# eae-pld.net
KiCad netlist of a schematic drawn in EAGLE
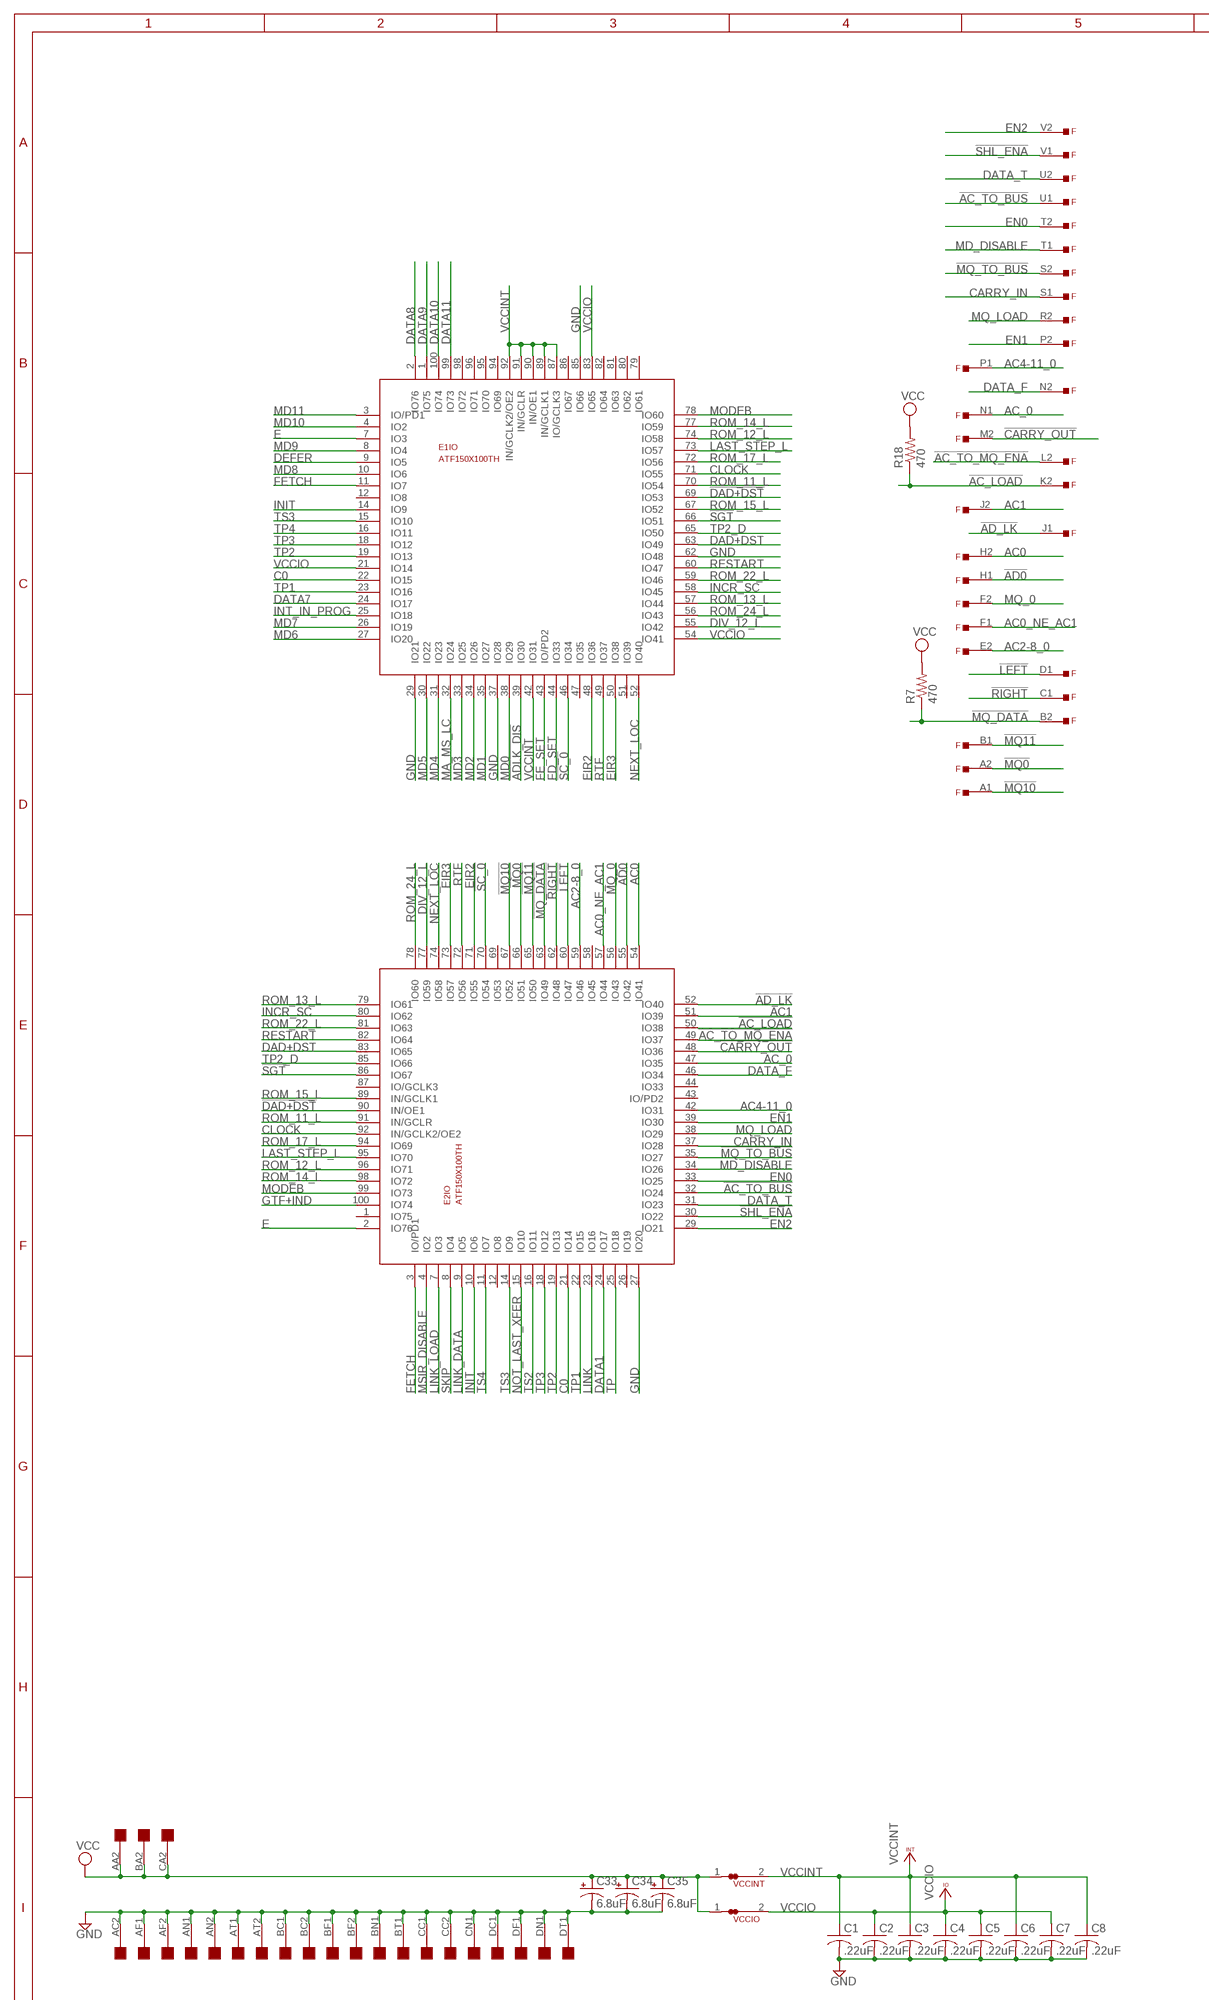
[diagram p0: schematic, sheet 1, part 1 of 2]
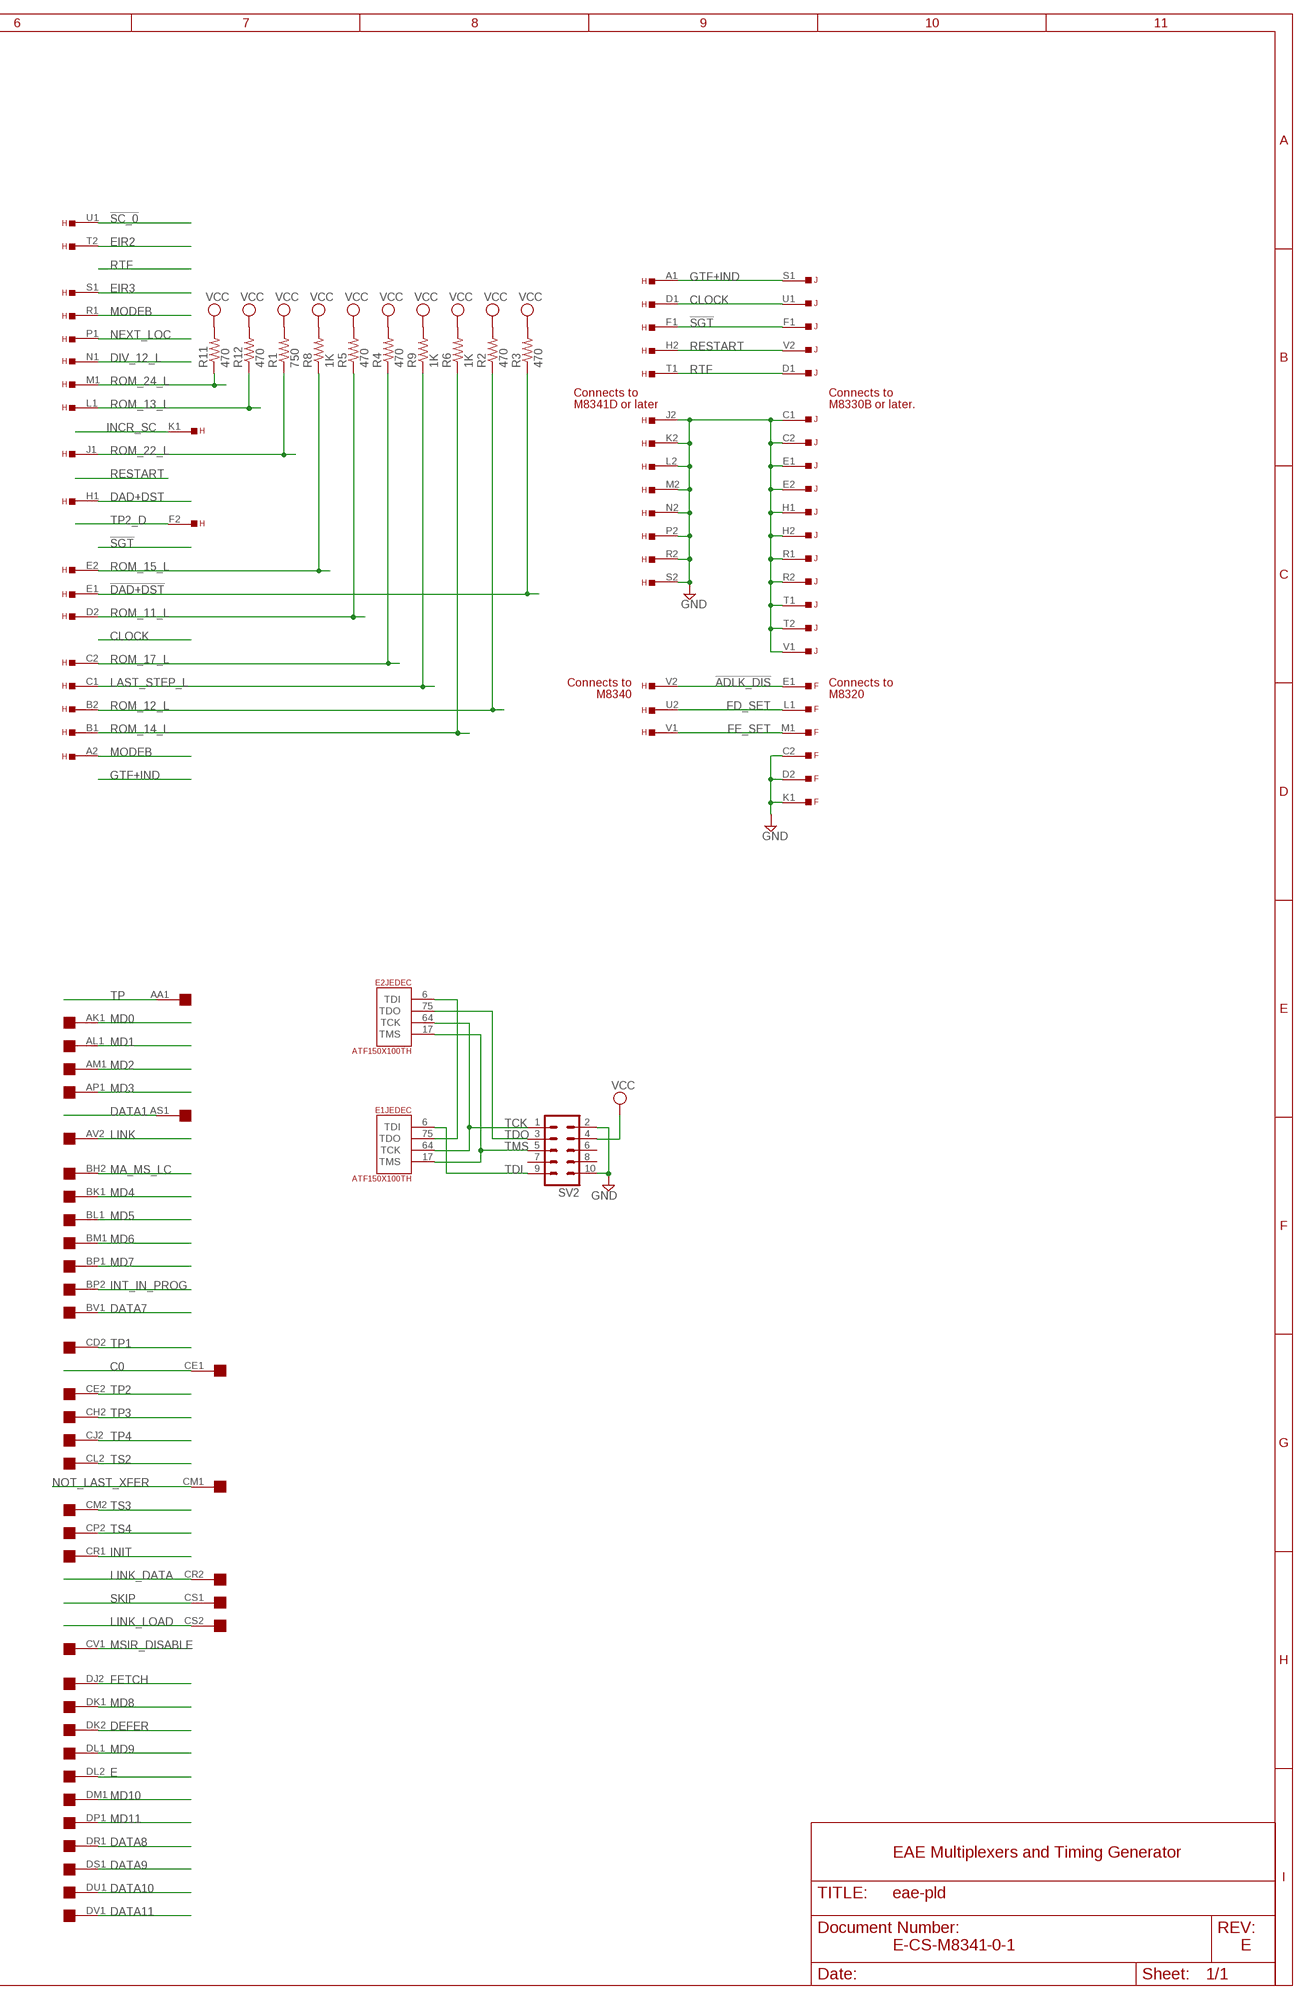
[diagram p1: schematic, sheet 1, part 2 of 2]

(export (version "E")
  (design (tool "Eeschema 10.0.6"))
  (components
    (comp (ref "C1")
      (value ".22uF")
      (footprint "eagle-import:C063-025X075")
      (libsource (lib "eagle-import") (part "C-US"))
    )
    (comp (ref "C2")
      (value ".22uF")
      (footprint "eagle-import:C063-025X075")
      (libsource (lib "eagle-import") (part "C-US"))
    )
    (comp (ref "C3")
      (value ".22uF")
      (footprint "eagle-import:C063-025X075")
      (libsource (lib "eagle-import") (part "C-US"))
    )
    (comp (ref "C4")
      (value ".22uF")
      (footprint "eagle-import:C063-025X075")
      (libsource (lib "eagle-import") (part "C-US"))
    )
    (comp (ref "C5")
      (value ".22uF")
      (footprint "eagle-import:C063-025X075")
      (libsource (lib "eagle-import") (part "C-US"))
    )
    (comp (ref "C6")
      (value ".22uF")
      (footprint "eagle-import:C063-025X075")
      (libsource (lib "eagle-import") (part "C-US"))
    )
    (comp (ref "C7")
      (value ".22uF")
      (footprint "eagle-import:C063-025X075")
      (libsource (lib "eagle-import") (part "C-US"))
    )
    (comp (ref "C8")
      (value ".22uF")
      (footprint "eagle-import:C063-025X075")
      (libsource (lib "eagle-import") (part "C-US"))
    )
    (comp (ref "C33")
      (value "6.8uF")
      (footprint "eagle-import:E12-8")
      (libsource (lib "eagle-import") (part "CPOL-USE20-8AXIAL"))
    )
    (comp (ref "C34")
      (value "6.8uF")
      (footprint "eagle-import:E12-8")
      (libsource (lib "eagle-import") (part "CPOL-USE20-8AXIAL"))
    )
    (comp (ref "C35")
      (value "6.8uF")
      (footprint "eagle-import:E12-8")
      (libsource (lib "eagle-import") (part "CPOL-USE20-8AXIAL"))
    )
    (comp (ref "E1")
      (value "ATF150X100TH")
      (footprint "eagle-import:TH-100")
      (libsource (lib "eagle-import") (part "ATF150X100TH"))
    )
    (comp (ref "E2")
      (value "ATF150X100TH")
      (footprint "eagle-import:TH-100")
      (libsource (lib "eagle-import") (part "ATF150X100TH"))
    )
    (comp (ref "F")
      (value "EDGE-TOP")
      (footprint "eagle-import:EDGE-CON2")
      (libsource (lib "eagle-import") (part "EDGE-TOP"))
    )
    (comp (ref "H")
      (value "EDGE-TOP")
      (footprint "eagle-import:EDGE-CON2")
      (libsource (lib "eagle-import") (part "EDGE-TOP"))
    )
    (comp (ref "J")
      (value "EDGE-TOP")
      (footprint "eagle-import:EDGE-CON2")
      (libsource (lib "eagle-import") (part "EDGE-TOP"))
    )
    (comp (ref "R1")
      (value "750")
      (footprint "eagle-import:0207_10")
      (libsource (lib "eagle-import") (part "R-US_0207/10"))
    )
    (comp (ref "R2")
      (value "470")
      (footprint "eagle-import:0207_10")
      (libsource (lib "eagle-import") (part "R-US_0207/10"))
    )
    (comp (ref "R3")
      (value "470")
      (footprint "eagle-import:0207_10")
      (libsource (lib "eagle-import") (part "R-US_0207/10"))
    )
    (comp (ref "R4")
      (value "470")
      (footprint "eagle-import:0207_10")
      (libsource (lib "eagle-import") (part "R-US_0207/10"))
    )
    (comp (ref "R5")
      (value "470")
      (footprint "eagle-import:0207_10")
      (libsource (lib "eagle-import") (part "R-US_0207/10"))
    )
    (comp (ref "R6")
      (value "1K")
      (footprint "eagle-import:0207_10")
      (libsource (lib "eagle-import") (part "R-US_0207/10"))
    )
    (comp (ref "R7")
      (value "470")
      (footprint "eagle-import:0207_10")
      (libsource (lib "eagle-import") (part "R-US_0207/10"))
    )
    (comp (ref "R8")
      (value "1K")
      (footprint "eagle-import:0207_10")
      (libsource (lib "eagle-import") (part "R-US_0207/10"))
    )
    (comp (ref "R9")
      (value "1K")
      (footprint "eagle-import:0207_10")
      (libsource (lib "eagle-import") (part "R-US_0207/10"))
    )
    (comp (ref "R11")
      (value "470")
      (footprint "eagle-import:0207_10")
      (libsource (lib "eagle-import") (part "R-US_0207/10"))
    )
    (comp (ref "R12")
      (value "470")
      (footprint "eagle-import:0207_10")
      (libsource (lib "eagle-import") (part "R-US_0207/10"))
    )
    (comp (ref "R18")
      (value "470")
      (footprint "eagle-import:0207_10")
      (libsource (lib "eagle-import") (part "R-US_0207/10"))
    )
    (comp (ref "SV2")
      (value "ML10")
      (footprint "eagle-import:ML10")
      (libsource (lib "eagle-import") (part "ML10"))
    )
    (comp (ref "U$1")
      (value "QUAD")
      (footprint "eagle-import:EDGE-CON8")
      (libsource (lib "eagle-import") (part "QUAD"))
    )
    (comp (ref "VCCINT")
      (value "JUMPER-NC1")
      (footprint "eagle-import:NC1")
      (libsource (lib "eagle-import") (part "JUMPER-NC1"))
    )
    (comp (ref "VCCIO")
      (value "JUMPER-NC1")
      (footprint "eagle-import:NC1")
      (libsource (lib "eagle-import") (part "JUMPER-NC1"))
    )
  )
  (nets
    (net (code "1") (name "/AC0") (class "Default")
      (node (ref "E2") (pin "54") (pinfunction "IO41_54") (pintype "bidirectional"))
      (node (ref "F") (pin "H2") (pinfunction "P_H2") (pintype "passive"))
    )
    (net (code "2") (name "/AC0_NE_AC1") (class "Default")
      (node (ref "E2") (pin "57") (pinfunction "IO44_57") (pintype "bidirectional"))
      (node (ref "F") (pin "F1") (pinfunction "P_F1") (pintype "passive"))
    )
    (net (code "3") (name "/AC1") (class "Default")
      (node (ref "E2") (pin "51") (pinfunction "IO39_51") (pintype "bidirectional"))
      (node (ref "F") (pin "J2") (pinfunction "P_J2") (pintype "passive"))
    )
    (net (code "4") (name "/AC2-8_0") (class "Default")
      (node (ref "E2") (pin "59") (pinfunction "IO46_59") (pintype "bidirectional"))
      (node (ref "F") (pin "E2") (pinfunction "P_E2") (pintype "passive"))
    )
    (net (code "5") (name "/AC4-11_0") (class "Default")
      (node (ref "E2") (pin "42") (pinfunction "IO31_42") (pintype "bidirectional"))
      (node (ref "F") (pin "P1") (pinfunction "P_P1") (pintype "passive"))
    )
    (net (code "6") (name "/AC_0") (class "Default")
      (node (ref "E2") (pin "47") (pinfunction "IO35_47") (pintype "bidirectional"))
      (node (ref "F") (pin "N1") (pinfunction "P_N1") (pintype "passive"))
    )
    (net (code "7") (name "/C0") (class "Default")
      (node (ref "E1") (pin "22") (pinfunction "IO15_22") (pintype "bidirectional"))
      (node (ref "E2") (pin "21") (pinfunction "IO14_21") (pintype "bidirectional"))
      (node (ref "U$1") (pin "CE1") (pinfunction "1_CE1") (pintype "bidirectional"))
    )
    (net (code "8") (name "/CARRY_IN") (class "Default")
      (node (ref "E2") (pin "37") (pinfunction "IO28_37") (pintype "bidirectional"))
      (node (ref "F") (pin "S1") (pinfunction "P_S1") (pintype "passive"))
    )
    (net (code "9") (name "/CLOCK") (class "Default")
      (node (ref "E1") (pin "71") (pinfunction "IO55_71") (pintype "bidirectional"))
      (node (ref "E2") (pin "92") (pinfunction "IN/GCLK2/OE2_92") (pintype "input"))
      (node (ref "H") (pin "D1") (pinfunction "P_D1") (pintype "passive"))
      (node (ref "J") (pin "U1") (pinfunction "P_U1") (pintype "passive"))
    )
    (net (code "10") (name "/DAD+DST") (class "Default")
      (node (ref "E1") (pin "63") (pinfunction "IO49_63") (pintype "bidirectional"))
      (node (ref "E2") (pin "83") (pinfunction "IO65_83") (pintype "bidirectional"))
      (node (ref "H") (pin "H1") (pinfunction "P_H1") (pintype "passive"))
    )
    (net (code "11") (name "/DATA1") (class "Default")
      (node (ref "E2") (pin "24") (pinfunction "IO17_24") (pintype "bidirectional"))
      (node (ref "U$1") (pin "AS1") (pinfunction "1_AS1") (pintype "bidirectional"))
    )
    (net (code "12") (name "/DATA7") (class "Default")
      (node (ref "E1") (pin "24") (pinfunction "IO17_24") (pintype "bidirectional"))
      (node (ref "U$1") (pin "BV1") (pinfunction "1_BV1") (pintype "bidirectional"))
    )
    (net (code "13") (name "/DATA8") (class "Default")
      (node (ref "E1") (pin "2") (pinfunction "IO76_2") (pintype "bidirectional"))
      (node (ref "U$1") (pin "DR1") (pinfunction "1_DR1") (pintype "bidirectional"))
    )
    (net (code "14") (name "/DATA9") (class "Default")
      (node (ref "E1") (pin "1") (pinfunction "IO75_1") (pintype "bidirectional"))
      (node (ref "U$1") (pin "DS1") (pinfunction "1_DS1") (pintype "bidirectional"))
    )
    (net (code "15") (name "/DATA10") (class "Default")
      (node (ref "E1") (pin "100") (pinfunction "IO74_100") (pintype "bidirectional"))
      (node (ref "U$1") (pin "DU1") (pinfunction "1_DU1") (pintype "bidirectional"))
    )
    (net (code "16") (name "/DATA11") (class "Default")
      (node (ref "E1") (pin "99") (pinfunction "IO73_99") (pintype "bidirectional"))
      (node (ref "U$1") (pin "DV1") (pinfunction "1_DV1") (pintype "bidirectional"))
    )
    (net (code "17") (name "/DATA_F") (class "Default")
      (node (ref "E2") (pin "46") (pinfunction "IO34_46") (pintype "bidirectional"))
      (node (ref "F") (pin "N2") (pinfunction "P_N2") (pintype "passive"))
    )
    (net (code "18") (name "/DATA_T") (class "Default")
      (node (ref "E2") (pin "31") (pinfunction "IO23_31") (pintype "bidirectional"))
      (node (ref "F") (pin "U2") (pinfunction "P_U2") (pintype "passive"))
    )
    (net (code "19") (name "/DEFER") (class "Default")
      (node (ref "E1") (pin "9") (pinfunction "IO5_9") (pintype "bidirectional"))
      (node (ref "U$1") (pin "DK2") (pinfunction "1_DK2") (pintype "bidirectional"))
    )
    (net (code "20") (name "/DIV_12_L") (class "Default")
      (node (ref "E1") (pin "55") (pinfunction "IO42_55") (pintype "bidirectional"))
      (node (ref "E2") (pin "77") (pinfunction "IO59_77") (pintype "bidirectional"))
      (node (ref "H") (pin "N1") (pinfunction "P_N1") (pintype "passive"))
    )
    (net (code "21") (name "/E") (class "Default")
      (node (ref "E1") (pin "7") (pinfunction "IO3_7") (pintype "bidirectional"))
      (node (ref "E2") (pin "2") (pinfunction "IO76_2") (pintype "bidirectional"))
      (node (ref "U$1") (pin "DL2") (pinfunction "1_DL2") (pintype "bidirectional"))
    )
    (net (code "22") (name "/EIR2") (class "Default")
      (node (ref "E1") (pin "48") (pinfunction "IO36_48") (pintype "bidirectional"))
      (node (ref "E2") (pin "71") (pinfunction "IO55_71") (pintype "bidirectional"))
      (node (ref "H") (pin "T2") (pinfunction "P_T2") (pintype "passive"))
    )
    (net (code "23") (name "/EIR3") (class "Default")
      (node (ref "E1") (pin "50") (pinfunction "IO38_50") (pintype "bidirectional"))
      (node (ref "E2") (pin "73") (pinfunction "IO57_73") (pintype "bidirectional"))
      (node (ref "H") (pin "S1") (pinfunction "P_S1") (pintype "passive"))
    )
    (net (code "24") (name "/EN0") (class "Default")
      (node (ref "E2") (pin "33") (pinfunction "IO25_33") (pintype "bidirectional"))
      (node (ref "F") (pin "T2") (pinfunction "P_T2") (pintype "passive"))
    )
    (net (code "25") (name "/EN1") (class "Default")
      (node (ref "E2") (pin "39") (pinfunction "IO30_39") (pintype "bidirectional"))
      (node (ref "F") (pin "P2") (pinfunction "P_P2") (pintype "passive"))
    )
    (net (code "26") (name "/EN2") (class "Default")
      (node (ref "E2") (pin "29") (pinfunction "IO21_29") (pintype "bidirectional"))
      (node (ref "F") (pin "V2") (pinfunction "P_V2") (pintype "passive"))
    )
    (net (code "27") (name "/FD_SET") (class "Default")
      (node (ref "E1") (pin "44") (pinfunction "IO33_44") (pintype "bidirectional"))
      (node (ref "F") (pin "L1") (pinfunction "P_L1") (pintype "passive"))
      (node (ref "H") (pin "U2") (pinfunction "P_U2") (pintype "passive"))
    )
    (net (code "28") (name "/FETCH") (class "Default")
      (node (ref "E1") (pin "11") (pinfunction "IO7_11") (pintype "bidirectional"))
      (node (ref "E2") (pin "3") (pinfunction "IO/PD1_3") (pintype "bidirectional"))
      (node (ref "U$1") (pin "DJ2") (pinfunction "1_DJ2") (pintype "bidirectional"))
    )
    (net (code "29") (name "/FE_SET") (class "Default")
      (node (ref "E1") (pin "43") (pinfunction "IO/PD2_43") (pintype "bidirectional"))
      (node (ref "F") (pin "M1") (pinfunction "P_M1") (pintype "passive"))
      (node (ref "H") (pin "V1") (pinfunction "P_V1") (pintype "passive"))
    )
    (net (code "30") (name "/GTF+IND") (class "Default")
      (node (ref "E2") (pin "100") (pinfunction "IO74_100") (pintype "bidirectional"))
      (node (ref "H") (pin "A1") (pinfunction "P_A1") (pintype "passive"))
      (node (ref "J") (pin "S1") (pinfunction "P_S1") (pintype "passive"))
    )
    (net (code "31") (name "/INCR_SC") (class "Default")
      (node (ref "E1") (pin "58") (pinfunction "IO45_58") (pintype "bidirectional"))
      (node (ref "E2") (pin "80") (pinfunction "IO62_80") (pintype "bidirectional"))
      (node (ref "H") (pin "K1") (pinfunction "P_K1") (pintype "passive"))
    )
    (net (code "32") (name "/INIT") (class "Default")
      (node (ref "E1") (pin "14") (pinfunction "IO9_14") (pintype "bidirectional"))
      (node (ref "E2") (pin "10") (pinfunction "IO6_10") (pintype "bidirectional"))
      (node (ref "U$1") (pin "CR1") (pinfunction "1_CR1") (pintype "bidirectional"))
    )
    (net (code "33") (name "/INT_IN_PROG") (class "Default")
      (node (ref "E1") (pin "25") (pinfunction "IO18_25") (pintype "bidirectional"))
      (node (ref "U$1") (pin "BP2") (pinfunction "1_BP2") (pintype "bidirectional"))
    )
    (net (code "34") (name "/LAST_STEP_L") (class "Default")
      (node (ref "E1") (pin "73") (pinfunction "IO57_73") (pintype "bidirectional"))
      (node (ref "E2") (pin "95") (pinfunction "IO70_95") (pintype "bidirectional"))
      (node (ref "H") (pin "C1") (pinfunction "P_C1") (pintype "passive"))
      (node (ref "R9") (pin "1") (pinfunction "1_1") (pintype "passive"))
    )
    (net (code "35") (name "/LINK") (class "Default")
      (node (ref "E2") (pin "23") (pinfunction "IO16_23") (pintype "bidirectional"))
      (node (ref "U$1") (pin "AV2") (pinfunction "1_AV2") (pintype "bidirectional"))
    )
    (net (code "36") (name "/LINK_DATA") (class "Default")
      (node (ref "E2") (pin "9") (pinfunction "IO5_9") (pintype "bidirectional"))
      (node (ref "U$1") (pin "CR2") (pinfunction "1_CR2") (pintype "bidirectional"))
    )
    (net (code "37") (name "/LINK_LOAD") (class "Default")
      (node (ref "E2") (pin "7") (pinfunction "IO3_7") (pintype "bidirectional"))
      (node (ref "U$1") (pin "CS2") (pinfunction "1_CS2") (pintype "bidirectional"))
    )
    (net (code "38") (name "/MA_MS_LC") (class "Default")
      (node (ref "E1") (pin "32") (pinfunction "IO24_32") (pintype "bidirectional"))
      (node (ref "U$1") (pin "BH2") (pinfunction "1_BH2") (pintype "bidirectional"))
    )
    (net (code "39") (name "/MD0") (class "Default")
      (node (ref "E1") (pin "38") (pinfunction "IO29_38") (pintype "bidirectional"))
      (node (ref "U$1") (pin "AK1") (pinfunction "1_AK1") (pintype "bidirectional"))
    )
    (net (code "40") (name "/MD1") (class "Default")
      (node (ref "E1") (pin "35") (pinfunction "IO27_35") (pintype "bidirectional"))
      (node (ref "U$1") (pin "AL1") (pinfunction "1_AL1") (pintype "bidirectional"))
    )
    (net (code "41") (name "/MD2") (class "Default")
      (node (ref "E1") (pin "34") (pinfunction "IO26_34") (pintype "bidirectional"))
      (node (ref "U$1") (pin "AM1") (pinfunction "1_AM1") (pintype "bidirectional"))
    )
    (net (code "42") (name "/MD3") (class "Default")
      (node (ref "E1") (pin "33") (pinfunction "IO25_33") (pintype "bidirectional"))
      (node (ref "U$1") (pin "AP1") (pinfunction "1_AP1") (pintype "bidirectional"))
    )
    (net (code "43") (name "/MD4") (class "Default")
      (node (ref "E1") (pin "31") (pinfunction "IO23_31") (pintype "bidirectional"))
      (node (ref "U$1") (pin "BK1") (pinfunction "1_BK1") (pintype "bidirectional"))
    )
    (net (code "44") (name "/MD5") (class "Default")
      (node (ref "E1") (pin "30") (pinfunction "IO22_30") (pintype "bidirectional"))
      (node (ref "U$1") (pin "BL1") (pinfunction "1_BL1") (pintype "bidirectional"))
    )
    (net (code "45") (name "/MD6") (class "Default")
      (node (ref "E1") (pin "27") (pinfunction "IO20_27") (pintype "bidirectional"))
      (node (ref "U$1") (pin "BM1") (pinfunction "1_BM1") (pintype "bidirectional"))
    )
    (net (code "46") (name "/MD7") (class "Default")
      (node (ref "E1") (pin "26") (pinfunction "IO19_26") (pintype "bidirectional"))
      (node (ref "U$1") (pin "BP1") (pinfunction "1_BP1") (pintype "bidirectional"))
    )
    (net (code "47") (name "/MD8") (class "Default")
      (node (ref "E1") (pin "10") (pinfunction "IO6_10") (pintype "bidirectional"))
      (node (ref "U$1") (pin "DK1") (pinfunction "1_DK1") (pintype "bidirectional"))
    )
    (net (code "48") (name "/MD9") (class "Default")
      (node (ref "E1") (pin "8") (pinfunction "IO4_8") (pintype "bidirectional"))
      (node (ref "U$1") (pin "DL1") (pinfunction "1_DL1") (pintype "bidirectional"))
    )
    (net (code "49") (name "/MD10") (class "Default")
      (node (ref "E1") (pin "4") (pinfunction "IO2_4") (pintype "bidirectional"))
      (node (ref "U$1") (pin "DM1") (pinfunction "1_DM1") (pintype "bidirectional"))
    )
    (net (code "50") (name "/MD11") (class "Default")
      (node (ref "E1") (pin "3") (pinfunction "IO/PD1_3") (pintype "bidirectional"))
      (node (ref "U$1") (pin "DP1") (pinfunction "1_DP1") (pintype "bidirectional"))
    )
    (net (code "51") (name "/MD_DISABLE") (class "Default")
      (node (ref "E2") (pin "34") (pinfunction "IO26_34") (pintype "bidirectional"))
      (node (ref "F") (pin "T1") (pinfunction "P_T1") (pintype "passive"))
    )
    (net (code "52") (name "/MODEB") (class "Default")
      (node (ref "E1") (pin "78") (pinfunction "IO60_78") (pintype "bidirectional"))
      (node (ref "E2") (pin "99") (pinfunction "IO73_99") (pintype "bidirectional"))
      (node (ref "H") (pin "A2") (pinfunction "P_A2") (pintype "passive"))
      (node (ref "H") (pin "R1") (pinfunction "P_R1") (pintype "passive"))
    )
    (net (code "53") (name "/MQ_0") (class "Default")
      (node (ref "E2") (pin "56") (pinfunction "IO43_56") (pintype "bidirectional"))
      (node (ref "F") (pin "F2") (pinfunction "P_F2") (pintype "passive"))
    )
    (net (code "54") (name "/MQ_LOAD") (class "Default")
      (node (ref "E2") (pin "38") (pinfunction "IO29_38") (pintype "bidirectional"))
      (node (ref "F") (pin "R2") (pinfunction "P_R2") (pintype "passive"))
    )
    (net (code "55") (name "/MSIR_DISABLE") (class "Default")
      (node (ref "E2") (pin "4") (pinfunction "IO2_4") (pintype "bidirectional"))
      (node (ref "U$1") (pin "CV1") (pinfunction "1_CV1") (pintype "bidirectional"))
    )
    (net (code "56") (name "/NEXT_LOC") (class "Default")
      (node (ref "E1") (pin "52") (pinfunction "IO40_52") (pintype "bidirectional"))
      (node (ref "E2") (pin "74") (pinfunction "IO58_74") (pintype "bidirectional"))
      (node (ref "H") (pin "P1") (pinfunction "P_P1") (pintype "passive"))
    )
    (net (code "57") (name "/NOT_LAST_XFER") (class "Default")
      (node (ref "E2") (pin "15") (pinfunction "IO10_15") (pintype "bidirectional"))
      (node (ref "U$1") (pin "CM1") (pinfunction "1_CM1") (pintype "bidirectional"))
    )
    (net (code "58") (name "/RESTART") (class "Default")
      (node (ref "E1") (pin "60") (pinfunction "IO47_60") (pintype "bidirectional"))
      (node (ref "E2") (pin "82") (pinfunction "IO64_82") (pintype "bidirectional"))
      (node (ref "H") (pin "H2") (pinfunction "P_H2") (pintype "passive"))
      (node (ref "J") (pin "V2") (pinfunction "P_V2") (pintype "passive"))
    )
    (net (code "59") (name "/ROM_11_L") (class "Default")
      (node (ref "E1") (pin "70") (pinfunction "IO54_70") (pintype "bidirectional"))
      (node (ref "E2") (pin "91") (pinfunction "IN/GCLR_91") (pintype "input"))
      (node (ref "H") (pin "D2") (pinfunction "P_D2") (pintype "passive"))
      (node (ref "R5") (pin "1") (pinfunction "1_1") (pintype "passive"))
    )
    (net (code "60") (name "/ROM_12_L") (class "Default")
      (node (ref "E1") (pin "74") (pinfunction "IO58_74") (pintype "bidirectional"))
      (node (ref "E2") (pin "96") (pinfunction "IO71_96") (pintype "bidirectional"))
      (node (ref "H") (pin "B2") (pinfunction "P_B2") (pintype "passive"))
      (node (ref "R2") (pin "1") (pinfunction "1_1") (pintype "passive"))
    )
    (net (code "61") (name "/ROM_13_L") (class "Default")
      (node (ref "E1") (pin "57") (pinfunction "IO44_57") (pintype "bidirectional"))
      (node (ref "E2") (pin "79") (pinfunction "IO61_79") (pintype "bidirectional"))
      (node (ref "H") (pin "L1") (pinfunction "P_L1") (pintype "passive"))
      (node (ref "R12") (pin "1") (pinfunction "1_1") (pintype "passive"))
    )
    (net (code "62") (name "/ROM_14_L") (class "Default")
      (node (ref "E1") (pin "77") (pinfunction "IO59_77") (pintype "bidirectional"))
      (node (ref "E2") (pin "98") (pinfunction "IO72_98") (pintype "bidirectional"))
      (node (ref "H") (pin "B1") (pinfunction "P_B1") (pintype "passive"))
      (node (ref "R6") (pin "1") (pinfunction "1_1") (pintype "passive"))
    )
    (net (code "63") (name "/ROM_15_L") (class "Default")
      (node (ref "E1") (pin "67") (pinfunction "IO52_67") (pintype "bidirectional"))
      (node (ref "E2") (pin "89") (pinfunction "IN/GCLK1_89") (pintype "input"))
      (node (ref "H") (pin "E2") (pinfunction "P_E2") (pintype "passive"))
      (node (ref "R8") (pin "1") (pinfunction "1_1") (pintype "passive"))
    )
    (net (code "64") (name "/ROM_17_L") (class "Default")
      (node (ref "E1") (pin "72") (pinfunction "IO56_72") (pintype "bidirectional"))
      (node (ref "E2") (pin "94") (pinfunction "IO69_94") (pintype "bidirectional"))
      (node (ref "H") (pin "C2") (pinfunction "P_C2") (pintype "passive"))
      (node (ref "R4") (pin "1") (pinfunction "1_1") (pintype "passive"))
    )
    (net (code "65") (name "/ROM_22_L") (class "Default")
      (node (ref "E1") (pin "59") (pinfunction "IO46_59") (pintype "bidirectional"))
      (node (ref "E2") (pin "81") (pinfunction "IO63_81") (pintype "bidirectional"))
      (node (ref "H") (pin "J1") (pinfunction "P_J1") (pintype "passive"))
      (node (ref "R1") (pin "1") (pinfunction "1_1") (pintype "passive"))
    )
    (net (code "66") (name "/ROM_24_L") (class "Default")
      (node (ref "E1") (pin "56") (pinfunction "IO43_56") (pintype "bidirectional"))
      (node (ref "E2") (pin "78") (pinfunction "IO60_78") (pintype "bidirectional"))
      (node (ref "H") (pin "M1") (pinfunction "P_M1") (pintype "passive"))
      (node (ref "R11") (pin "1") (pinfunction "1_1") (pintype "passive"))
    )
    (net (code "67") (name "/RTF") (class "Default")
      (node (ref "E1") (pin "49") (pinfunction "IO37_49") (pintype "bidirectional"))
      (node (ref "E2") (pin "72") (pinfunction "IO56_72") (pintype "bidirectional"))
      (node (ref "H") (pin "T1") (pinfunction "P_T1") (pintype "passive"))
      (node (ref "J") (pin "D1") (pinfunction "P_D1") (pintype "passive"))
    )
    (net (code "68") (name "/SKIP") (class "Default")
      (node (ref "E2") (pin "8") (pinfunction "IO4_8") (pintype "bidirectional"))
      (node (ref "U$1") (pin "CS1") (pinfunction "1_CS1") (pintype "bidirectional"))
    )
    (net (code "69") (name "/TCK") (class "Default")
      (node (ref "E1") (pin "64") (pinfunction "TCK_64") (pintype "bidirectional"))
      (node (ref "E2") (pin "64") (pinfunction "TCK_64") (pintype "bidirectional"))
      (node (ref "SV2") (pin "1") (pinfunction "1_1") (pintype "passive"))
    )
    (net (code "70") (name "/TDI") (class "Default")
      (node (ref "E1") (pin "6") (pinfunction "TDI_6") (pintype "bidirectional"))
      (node (ref "SV2") (pin "9") (pinfunction "9_9") (pintype "passive"))
    )
    (net (code "71") (name "/TDO") (class "Default")
      (node (ref "E2") (pin "75") (pinfunction "TDO_75") (pintype "bidirectional"))
      (node (ref "SV2") (pin "3") (pinfunction "3_3") (pintype "passive"))
    )
    (net (code "72") (name "/TMS") (class "Default")
      (node (ref "E1") (pin "17") (pinfunction "TMS_17") (pintype "bidirectional"))
      (node (ref "E2") (pin "17") (pinfunction "TMS_17") (pintype "bidirectional"))
      (node (ref "SV2") (pin "5") (pinfunction "5_5") (pintype "passive"))
    )
    (net (code "73") (name "/TP") (class "Default")
      (node (ref "E2") (pin "25") (pinfunction "IO18_25") (pintype "bidirectional"))
      (node (ref "U$1") (pin "AA1") (pinfunction "1_AA1") (pintype "bidirectional"))
    )
    (net (code "74") (name "/TP1") (class "Default")
      (node (ref "E1") (pin "23") (pinfunction "IO16_23") (pintype "bidirectional"))
      (node (ref "E2") (pin "22") (pinfunction "IO15_22") (pintype "bidirectional"))
      (node (ref "U$1") (pin "CD2") (pinfunction "1_CD2") (pintype "bidirectional"))
    )
    (net (code "75") (name "/TP2") (class "Default")
      (node (ref "E1") (pin "19") (pinfunction "IO13_19") (pintype "bidirectional"))
      (node (ref "E2") (pin "19") (pinfunction "IO13_19") (pintype "bidirectional"))
      (node (ref "U$1") (pin "CE2") (pinfunction "1_CE2") (pintype "bidirectional"))
    )
    (net (code "76") (name "/TP2_D") (class "Default")
      (node (ref "E1") (pin "65") (pinfunction "IO50_65") (pintype "bidirectional"))
      (node (ref "E2") (pin "85") (pinfunction "IO66_85") (pintype "bidirectional"))
      (node (ref "H") (pin "F2") (pinfunction "P_F2") (pintype "passive"))
    )
    (net (code "77") (name "/TP3") (class "Default")
      (node (ref "E1") (pin "18") (pinfunction "IO12_18") (pintype "bidirectional"))
      (node (ref "E2") (pin "18") (pinfunction "IO12_18") (pintype "bidirectional"))
      (node (ref "U$1") (pin "CH2") (pinfunction "1_CH2") (pintype "bidirectional"))
    )
    (net (code "78") (name "/TP4") (class "Default")
      (node (ref "E1") (pin "16") (pinfunction "IO11_16") (pintype "bidirectional"))
      (node (ref "U$1") (pin "CJ2") (pinfunction "1_CJ2") (pintype "bidirectional"))
    )
    (net (code "79") (name "/TS2") (class "Default")
      (node (ref "E2") (pin "16") (pinfunction "IO11_16") (pintype "bidirectional"))
      (node (ref "U$1") (pin "CL2") (pinfunction "1_CL2") (pintype "bidirectional"))
    )
    (net (code "80") (name "/TS3") (class "Default")
      (node (ref "E1") (pin "15") (pinfunction "IO10_15") (pintype "bidirectional"))
      (node (ref "E2") (pin "14") (pinfunction "IO9_14") (pintype "bidirectional"))
      (node (ref "U$1") (pin "CM2") (pinfunction "1_CM2") (pintype "bidirectional"))
    )
    (net (code "81") (name "/TS4") (class "Default")
      (node (ref "E2") (pin "11") (pinfunction "IO7_11") (pintype "bidirectional"))
      (node (ref "U$1") (pin "CP2") (pinfunction "1_CP2") (pintype "bidirectional"))
    )
    (net (code "82") (name "/~{AC_LOAD}") (class "Default")
      (node (ref "E2") (pin "50") (pinfunction "IO38_50") (pintype "bidirectional"))
      (node (ref "F") (pin "K2") (pinfunction "P_K2") (pintype "passive"))
      (node (ref "R18") (pin "1") (pinfunction "1_1") (pintype "passive"))
    )
    (net (code "83") (name "/~{AC_TO_BUS}") (class "Default")
      (node (ref "E2") (pin "32") (pinfunction "IO24_32") (pintype "bidirectional"))
      (node (ref "F") (pin "U1") (pinfunction "P_U1") (pintype "passive"))
    )
    (net (code "84") (name "/~{AC_TO_MQ_ENA}") (class "Default")
      (node (ref "E2") (pin "49") (pinfunction "IO37_49") (pintype "bidirectional"))
      (node (ref "F") (pin "L2") (pinfunction "P_L2") (pintype "passive"))
    )
    (net (code "85") (name "/~{AD0}") (class "Default")
      (node (ref "E2") (pin "55") (pinfunction "IO42_55") (pintype "bidirectional"))
      (node (ref "F") (pin "H1") (pinfunction "P_H1") (pintype "passive"))
    )
    (net (code "86") (name "/~{ADLK_DIS}") (class "Default")
      (node (ref "E1") (pin "39") (pinfunction "IO30_39") (pintype "bidirectional"))
      (node (ref "F") (pin "E1") (pinfunction "P_E1") (pintype "passive"))
      (node (ref "H") (pin "V2") (pinfunction "P_V2") (pintype "passive"))
    )
    (net (code "87") (name "/~{AD_LK}") (class "Default")
      (node (ref "E2") (pin "52") (pinfunction "IO40_52") (pintype "bidirectional"))
      (node (ref "F") (pin "J1") (pinfunction "P_J1") (pintype "passive"))
    )
    (net (code "88") (name "/~{CARRY_OUT}") (class "Default")
      (node (ref "E2") (pin "48") (pinfunction "IO36_48") (pintype "bidirectional"))
      (node (ref "F") (pin "M2") (pinfunction "P_M2") (pintype "passive"))
    )
    (net (code "89") (name "/~{DAD+DST}") (class "Default")
      (node (ref "E1") (pin "69") (pinfunction "IO53_69") (pintype "bidirectional"))
      (node (ref "E2") (pin "90") (pinfunction "IN/OE1_90") (pintype "input"))
      (node (ref "H") (pin "E1") (pinfunction "P_E1") (pintype "passive"))
      (node (ref "R3") (pin "1") (pinfunction "1_1") (pintype "passive"))
    )
    (net (code "90") (name "/~{LEFT}") (class "Default")
      (node (ref "E2") (pin "60") (pinfunction "IO47_60") (pintype "bidirectional"))
      (node (ref "F") (pin "D1") (pinfunction "P_D1") (pintype "passive"))
    )
    (net (code "91") (name "/~{MQ0}") (class "Default")
      (node (ref "E2") (pin "66") (pinfunction "IO51_66") (pintype "bidirectional"))
      (node (ref "F") (pin "A2") (pinfunction "P_A2") (pintype "passive"))
    )
    (net (code "92") (name "/~{MQ10}") (class "Default")
      (node (ref "E2") (pin "67") (pinfunction "IO52_67") (pintype "bidirectional"))
      (node (ref "F") (pin "A1") (pinfunction "P_A1") (pintype "passive"))
    )
    (net (code "93") (name "/~{MQ11}") (class "Default")
      (node (ref "E2") (pin "65") (pinfunction "IO50_65") (pintype "bidirectional"))
      (node (ref "F") (pin "B1") (pinfunction "P_B1") (pintype "passive"))
    )
    (net (code "94") (name "/~{MQ_DATA}") (class "Default")
      (node (ref "E2") (pin "63") (pinfunction "IO49_63") (pintype "bidirectional"))
      (node (ref "F") (pin "B2") (pinfunction "P_B2") (pintype "passive"))
      (node (ref "R7") (pin "1") (pinfunction "1_1") (pintype "passive"))
    )
    (net (code "95") (name "/~{MQ_TO_BUS}") (class "Default")
      (node (ref "E2") (pin "35") (pinfunction "IO27_35") (pintype "bidirectional"))
      (node (ref "F") (pin "S2") (pinfunction "P_S2") (pintype "passive"))
    )
    (net (code "96") (name "/~{RIGHT}") (class "Default")
      (node (ref "E2") (pin "62") (pinfunction "IO48_62") (pintype "bidirectional"))
      (node (ref "F") (pin "C1") (pinfunction "P_C1") (pintype "passive"))
    )
    (net (code "97") (name "/~{SC_0}") (class "Default")
      (node (ref "E1") (pin "46") (pinfunction "IO34_46") (pintype "bidirectional"))
      (node (ref "E2") (pin "70") (pinfunction "IO54_70") (pintype "bidirectional"))
      (node (ref "H") (pin "U1") (pinfunction "P_U1") (pintype "passive"))
    )
    (net (code "98") (name "/~{SGT}") (class "Default")
      (node (ref "E1") (pin "66") (pinfunction "IO51_66") (pintype "bidirectional"))
      (node (ref "E2") (pin "86") (pinfunction "IO67_86") (pintype "bidirectional"))
      (node (ref "H") (pin "F1") (pinfunction "P_F1") (pintype "passive"))
      (node (ref "J") (pin "F1") (pinfunction "P_F1") (pintype "passive"))
    )
    (net (code "99") (name "/~{SHL_ENA}") (class "Default")
      (node (ref "E2") (pin "30") (pinfunction "IO22_30") (pintype "bidirectional"))
      (node (ref "F") (pin "V1") (pinfunction "P_V1") (pintype "passive"))
    )
    (net (code "100") (name "GND") (class "Default")
      (node (ref "C1") (pin "2") (pinfunction "2_2") (pintype "passive"))
      (node (ref "C2") (pin "2") (pinfunction "2_2") (pintype "passive"))
      (node (ref "C3") (pin "2") (pinfunction "2_2") (pintype "passive"))
      (node (ref "C33") (pin "-") (pinfunction "-_-") (pintype "passive"))
      (node (ref "C34") (pin "-") (pinfunction "-_-") (pintype "passive"))
      (node (ref "C35") (pin "-") (pinfunction "-_-") (pintype "passive"))
      (node (ref "C4") (pin "2") (pinfunction "2_2") (pintype "passive"))
      (node (ref "C5") (pin "2") (pinfunction "2_2") (pintype "passive"))
      (node (ref "C6") (pin "2") (pinfunction "2_2") (pintype "passive"))
      (node (ref "C7") (pin "2") (pinfunction "2_2") (pintype "passive"))
      (node (ref "C8") (pin "2") (pinfunction "2_2") (pintype "passive"))
      (node (ref "E1") (pin "29") (pinfunction "IO21_29") (pintype "bidirectional"))
      (node (ref "E1") (pin "37") (pinfunction "IO28_37") (pintype "bidirectional"))
      (node (ref "E1") (pin "62") (pinfunction "IO48_62") (pintype "bidirectional"))
      (node (ref "E1") (pin "85") (pinfunction "IO66_85") (pintype "bidirectional"))
      (node (ref "E2") (pin "27") (pinfunction "IO20_27") (pintype "bidirectional"))
      (node (ref "F") (pin "C2") (pinfunction "P_C2") (pintype "passive"))
      (node (ref "F") (pin "D2") (pinfunction "P_D2") (pintype "passive"))
      (node (ref "F") (pin "K1") (pinfunction "P_K1") (pintype "passive"))
      (node (ref "H") (pin "J2") (pinfunction "P_J2") (pintype "passive"))
      (node (ref "H") (pin "K2") (pinfunction "P_K2") (pintype "passive"))
      (node (ref "H") (pin "L2") (pinfunction "P_L2") (pintype "passive"))
      (node (ref "H") (pin "M2") (pinfunction "P_M2") (pintype "passive"))
      (node (ref "H") (pin "N2") (pinfunction "P_N2") (pintype "passive"))
      (node (ref "H") (pin "P2") (pinfunction "P_P2") (pintype "passive"))
      (node (ref "H") (pin "R2") (pinfunction "P_R2") (pintype "passive"))
      (node (ref "H") (pin "S2") (pinfunction "P_S2") (pintype "passive"))
      (node (ref "J") (pin "C1") (pinfunction "P_C1") (pintype "passive"))
      (node (ref "J") (pin "C2") (pinfunction "P_C2") (pintype "passive"))
      (node (ref "J") (pin "E1") (pinfunction "P_E1") (pintype "passive"))
      (node (ref "J") (pin "E2") (pinfunction "P_E2") (pintype "passive"))
      (node (ref "J") (pin "H1") (pinfunction "P_H1") (pintype "passive"))
      (node (ref "J") (pin "H2") (pinfunction "P_H2") (pintype "passive"))
      (node (ref "J") (pin "R1") (pinfunction "P_R1") (pintype "passive"))
      (node (ref "J") (pin "R2") (pinfunction "P_R2") (pintype "passive"))
      (node (ref "J") (pin "T1") (pinfunction "P_T1") (pintype "passive"))
      (node (ref "J") (pin "T2") (pinfunction "P_T2") (pintype "passive"))
      (node (ref "J") (pin "V1") (pinfunction "P_V1") (pintype "passive"))
      (node (ref "SV2") (pin "10") (pinfunction "10_10") (pintype "passive"))
      (node (ref "SV2") (pin "2") (pinfunction "2_2") (pintype "passive"))
      (node (ref "U$1") (pin "AC2") (pinfunction "1_AC2") (pintype "bidirectional"))
      (node (ref "U$1") (pin "AF1") (pinfunction "1_AF1") (pintype "bidirectional"))
      (node (ref "U$1") (pin "AF2") (pinfunction "1_AF2") (pintype "bidirectional"))
      (node (ref "U$1") (pin "AN1") (pinfunction "1_AN1") (pintype "bidirectional"))
      (node (ref "U$1") (pin "AN2") (pinfunction "1_AN2") (pintype "bidirectional"))
      (node (ref "U$1") (pin "AT1") (pinfunction "1_AT1") (pintype "bidirectional"))
      (node (ref "U$1") (pin "AT2") (pinfunction "1_AT2") (pintype "bidirectional"))
      (node (ref "U$1") (pin "BC1") (pinfunction "1_BC1") (pintype "bidirectional"))
      (node (ref "U$1") (pin "BC2") (pinfunction "1_BC2") (pintype "bidirectional"))
      (node (ref "U$1") (pin "BF1") (pinfunction "1_BF1") (pintype "bidirectional"))
      (node (ref "U$1") (pin "BF2") (pinfunction "1_BF2") (pintype "bidirectional"))
      (node (ref "U$1") (pin "BN1") (pinfunction "1_BN1") (pintype "bidirectional"))
      (node (ref "U$1") (pin "BT1") (pinfunction "1_BT1") (pintype "bidirectional"))
      (node (ref "U$1") (pin "CC1") (pinfunction "1_CC1") (pintype "bidirectional"))
      (node (ref "U$1") (pin "CC2") (pinfunction "1_CC2") (pintype "bidirectional"))
      (node (ref "U$1") (pin "CN1") (pinfunction "1_CN1") (pintype "bidirectional"))
      (node (ref "U$1") (pin "DC1") (pinfunction "1_DC1") (pintype "bidirectional"))
      (node (ref "U$1") (pin "DF1") (pinfunction "1_DF1") (pintype "bidirectional"))
      (node (ref "U$1") (pin "DN1") (pinfunction "1_DN1") (pintype "bidirectional"))
      (node (ref "U$1") (pin "DT1") (pinfunction "1_DT1") (pintype "bidirectional"))
    )
    (net (code "101") (name "Net-(E1R-TDO)") (class "Default")
      (node (ref "E1") (pin "75") (pinfunction "TDO_75") (pintype "bidirectional"))
      (node (ref "E2") (pin "6") (pinfunction "TDI_6") (pintype "bidirectional"))
    )
    (net (code "102") (name "VCC") (class "Default")
      (node (ref "C33") (pin "+") (pinfunction "+_+") (pintype "passive"))
      (node (ref "C34") (pin "+") (pinfunction "+_+") (pintype "passive"))
      (node (ref "C35") (pin "+") (pinfunction "+_+") (pintype "passive"))
      (node (ref "R1") (pin "2") (pinfunction "2_2") (pintype "passive"))
      (node (ref "R11") (pin "2") (pinfunction "2_2") (pintype "passive"))
      (node (ref "R12") (pin "2") (pinfunction "2_2") (pintype "passive"))
      (node (ref "R18") (pin "2") (pinfunction "2_2") (pintype "passive"))
      (node (ref "R2") (pin "2") (pinfunction "2_2") (pintype "passive"))
      (node (ref "R3") (pin "2") (pinfunction "2_2") (pintype "passive"))
      (node (ref "R4") (pin "2") (pinfunction "2_2") (pintype "passive"))
      (node (ref "R5") (pin "2") (pinfunction "2_2") (pintype "passive"))
      (node (ref "R6") (pin "2") (pinfunction "2_2") (pintype "passive"))
      (node (ref "R7") (pin "2") (pinfunction "2_2") (pintype "passive"))
      (node (ref "R8") (pin "2") (pinfunction "2_2") (pintype "passive"))
      (node (ref "R9") (pin "2") (pinfunction "2_2") (pintype "passive"))
      (node (ref "SV2") (pin "4") (pinfunction "4_4") (pintype "passive"))
      (node (ref "U$1") (pin "AA2") (pinfunction "1_AA2") (pintype "bidirectional"))
      (node (ref "U$1") (pin "BA2") (pinfunction "1_BA2") (pintype "bidirectional"))
      (node (ref "U$1") (pin "CA2") (pinfunction "1_CA2") (pintype "bidirectional"))
      (node (ref "VCCINT") (pin "1") (pinfunction "1_1") (pintype "bidirectional"))
      (node (ref "VCCIO") (pin "1") (pinfunction "1_1") (pintype "bidirectional"))
    )
    (net (code "103") (name "VCCINT") (class "Default")
      (node (ref "C1") (pin "1") (pinfunction "1_1") (pintype "passive"))
      (node (ref "C3") (pin "1") (pinfunction "1_1") (pintype "passive"))
      (node (ref "C6") (pin "1") (pinfunction "1_1") (pintype "passive"))
      (node (ref "C8") (pin "1") (pinfunction "1_1") (pintype "passive"))
      (node (ref "E1") (pin "42") (pinfunction "IO31_42") (pintype "bidirectional"))
      (node (ref "E1") (pin "87") (pinfunction "IO/GCLK3_87") (pintype "bidirectional"))
      (node (ref "E1") (pin "89") (pinfunction "IN/GCLK1_89") (pintype "input"))
      (node (ref "E1") (pin "90") (pinfunction "IN/OE1_90") (pintype "input"))
      (node (ref "E1") (pin "91") (pinfunction "IN/GCLR_91") (pintype "input"))
      (node (ref "E1") (pin "92") (pinfunction "IN/GCLK2/OE2_92") (pintype "input"))
      (node (ref "VCCINT") (pin "2") (pinfunction "2_2") (pintype "bidirectional"))
    )
    (net (code "104") (name "VCCIO") (class "Default")
      (node (ref "C2") (pin "1") (pinfunction "1_1") (pintype "passive"))
      (node (ref "C4") (pin "1") (pinfunction "1_1") (pintype "passive"))
      (node (ref "C5") (pin "1") (pinfunction "1_1") (pintype "passive"))
      (node (ref "C7") (pin "1") (pinfunction "1_1") (pintype "passive"))
      (node (ref "E1") (pin "21") (pinfunction "IO14_21") (pintype "bidirectional"))
      (node (ref "E1") (pin "54") (pinfunction "IO41_54") (pintype "bidirectional"))
      (node (ref "E1") (pin "83") (pinfunction "IO65_83") (pintype "bidirectional"))
      (node (ref "VCCIO") (pin "2") (pinfunction "2_2") (pintype "bidirectional"))
    )
    (net (code "105") (name "unconnected-(E1Q-IO8-Pad12)") (class "Default")
      (node (ref "E1") (pin "12") (pinfunction "IO8_12") (pintype "bidirectional"))
    )
    (net (code "106") (name "unconnected-(E1Q-IO35-Pad47)") (class "Default")
      (node (ref "E1") (pin "47") (pinfunction "IO35_47") (pintype "bidirectional"))
    )
    (net (code "107") (name "unconnected-(E1Q-IO39-Pad51)") (class "Default")
      (node (ref "E1") (pin "51") (pinfunction "IO39_51") (pintype "bidirectional"))
    )
    (net (code "108") (name "unconnected-(E1Q-IO61-Pad79)") (class "Default")
      (node (ref "E1") (pin "79") (pinfunction "IO61_79") (pintype "bidirectional"))
    )
    (net (code "109") (name "unconnected-(E1Q-IO62-Pad80)") (class "Default")
      (node (ref "E1") (pin "80") (pinfunction "IO62_80") (pintype "bidirectional"))
    )
    (net (code "110") (name "unconnected-(E1Q-IO63-Pad81)") (class "Default")
      (node (ref "E1") (pin "81") (pinfunction "IO63_81") (pintype "bidirectional"))
    )
    (net (code "111") (name "unconnected-(E1Q-IO64-Pad82)") (class "Default")
      (node (ref "E1") (pin "82") (pinfunction "IO64_82") (pintype "bidirectional"))
    )
    (net (code "112") (name "unconnected-(E1Q-IO67-Pad86)") (class "Default")
      (node (ref "E1") (pin "86") (pinfunction "IO67_86") (pintype "bidirectional"))
    )
    (net (code "113") (name "unconnected-(E1Q-IO69-Pad94)") (class "Default")
      (node (ref "E1") (pin "94") (pinfunction "IO69_94") (pintype "bidirectional"))
    )
    (net (code "114") (name "unconnected-(E1Q-IO70-Pad95)") (class "Default")
      (node (ref "E1") (pin "95") (pinfunction "IO70_95") (pintype "bidirectional"))
    )
    (net (code "115") (name "unconnected-(E1Q-IO71-Pad96)") (class "Default")
      (node (ref "E1") (pin "96") (pinfunction "IO71_96") (pintype "bidirectional"))
    )
    (net (code "116") (name "unconnected-(E1Q-IO72-Pad98)") (class "Default")
      (node (ref "E1") (pin "98") (pinfunction "IO72_98") (pintype "bidirectional"))
    )
    (net (code "117") (name "unconnected-(E2Q-IO8-Pad12)") (class "Default")
      (node (ref "E2") (pin "12") (pinfunction "IO8_12") (pintype "bidirectional"))
    )
    (net (code "118") (name "unconnected-(E2Q-IO19-Pad26)") (class "Default")
      (node (ref "E2") (pin "26") (pinfunction "IO19_26") (pintype "bidirectional"))
    )
    (net (code "119") (name "unconnected-(E2Q-IO33-Pad44)") (class "Default")
      (node (ref "E2") (pin "44") (pinfunction "IO33_44") (pintype "bidirectional"))
    )
    (net (code "120") (name "unconnected-(E2Q-IO45-Pad58)") (class "Default")
      (node (ref "E2") (pin "58") (pinfunction "IO45_58") (pintype "bidirectional"))
    )
    (net (code "121") (name "unconnected-(E2Q-IO53-Pad69)") (class "Default")
      (node (ref "E2") (pin "69") (pinfunction "IO53_69") (pintype "bidirectional"))
    )
    (net (code "122") (name "unconnected-(E2Q-IO75-Pad1)") (class "Default")
      (node (ref "E2") (pin "1") (pinfunction "IO75_1") (pintype "bidirectional"))
    )
    (net (code "123") (name "unconnected-(E2Q-IO{slash}GCLK3-Pad87)") (class "Default")
      (node (ref "E2") (pin "87") (pinfunction "IO/GCLK3_87") (pintype "bidirectional"))
    )
    (net (code "124") (name "unconnected-(E2Q-IO{slash}PD2-Pad43)") (class "Default")
      (node (ref "E2") (pin "43") (pinfunction "IO/PD2_43") (pintype "bidirectional"))
    )
    (net (code "125") (name "unconnected-(SV2-Pad6)") (class "Default")
      (node (ref "SV2") (pin "6") (pinfunction "6_6") (pintype "passive"))
    )
    (net (code "126") (name "unconnected-(SV2-Pad7)") (class "Default")
      (node (ref "SV2") (pin "7") (pinfunction "7_7") (pintype "passive"))
    )
    (net (code "127") (name "unconnected-(SV2-Pad8)") (class "Default")
      (node (ref "SV2") (pin "8") (pinfunction "8_8") (pintype "passive"))
    )
  )
)
